# Audio_Output_XLR2.net
KiCad netlist of a schematic drawn in Altium Designer
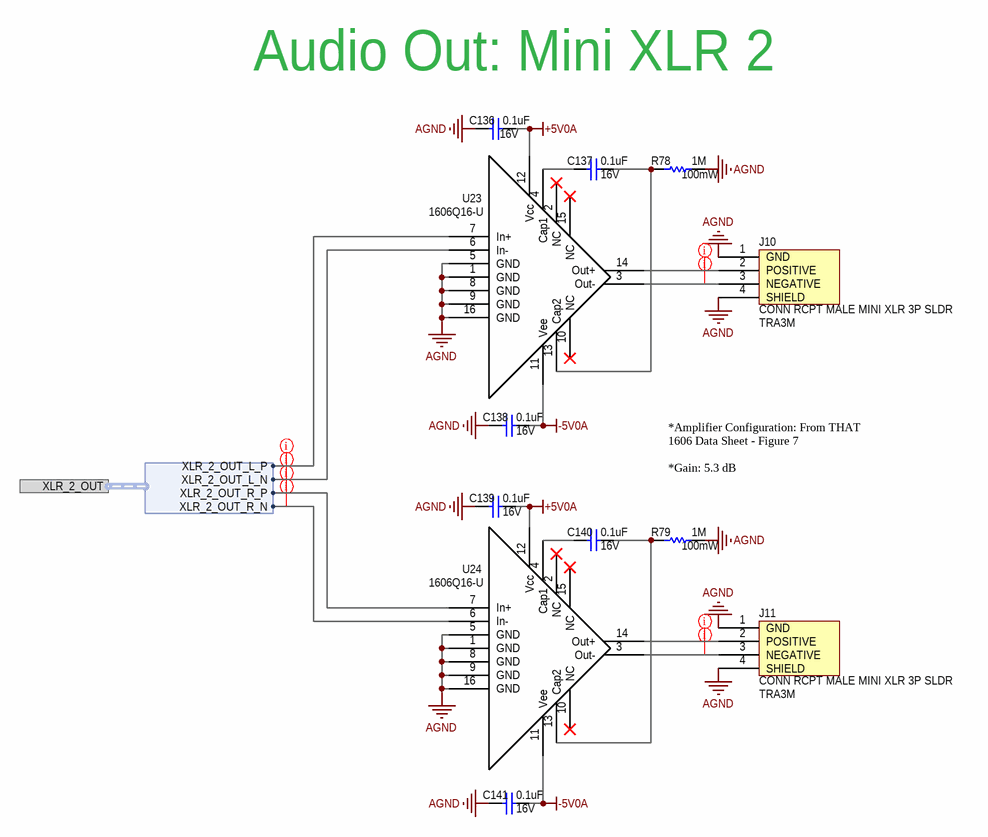
[diagram p0: Audio_Output_XLR2.SchDoc]

(export (version "E")
  (design (tool "Eeschema 10.0.6"))
  (components
    (comp (ref "C136")
      (value "CL10F104ZO8NNNC")
      (footprint "3-0603_L")
      (description "CAP CER 0.1UF 16V Y5V 0603")
      (fields
        (field (name "MANUFACTURER") "Samsung")
        (field (name "TOLERANCE") "80%")
        (field (name "VOLTAGE RATING") "16V")
        (field (name "CAPACITANCE") "0.1uF")
      )
      (libsource (lib "Schematic_Components_CD") (part "CL10F104ZO8NNNC"))
    )
    (comp (ref "C137")
      (value "CL10F104ZO8NNNC")
      (footprint "3-0603_L")
      (description "CAP CER 0.1UF 16V Y5V 0603")
      (fields
        (field (name "MANUFACTURER") "Samsung")
        (field (name "TOLERANCE") "80%")
        (field (name "VOLTAGE RATING") "16V")
        (field (name "CAPACITANCE") "0.1uF")
      )
      (libsource (lib "Schematic_Components_CD") (part "CL10F104ZO8NNNC"))
    )
    (comp (ref "C138")
      (value "CL10F104ZO8NNNC")
      (footprint "3-0603_L")
      (description "CAP CER 0.1UF 16V Y5V 0603")
      (fields
        (field (name "MANUFACTURER") "Samsung")
        (field (name "TOLERANCE") "80%")
        (field (name "VOLTAGE RATING") "16V")
        (field (name "CAPACITANCE") "0.1uF")
      )
      (libsource (lib "Schematic_Components_CD") (part "CL10F104ZO8NNNC"))
    )
    (comp (ref "C139")
      (value "CL10F104ZO8NNNC")
      (footprint "3-0603_L")
      (description "CAP CER 0.1UF 16V Y5V 0603")
      (fields
        (field (name "MANUFACTURER") "Samsung")
        (field (name "TOLERANCE") "80%")
        (field (name "VOLTAGE RATING") "16V")
        (field (name "CAPACITANCE") "0.1uF")
      )
      (libsource (lib "Schematic_Components_CD") (part "CL10F104ZO8NNNC"))
    )
    (comp (ref "C140")
      (value "CL10F104ZO8NNNC")
      (footprint "3-0603_L")
      (description "CAP CER 0.1UF 16V Y5V 0603")
      (fields
        (field (name "MANUFACTURER") "Samsung")
        (field (name "TOLERANCE") "80%")
        (field (name "VOLTAGE RATING") "16V")
        (field (name "CAPACITANCE") "0.1uF")
      )
      (libsource (lib "Schematic_Components_CD") (part "CL10F104ZO8NNNC"))
    )
    (comp (ref "C141")
      (value "CL10F104ZO8NNNC")
      (footprint "3-0603_L")
      (description "CAP CER 0.1UF 16V Y5V 0603")
      (fields
        (field (name "MANUFACTURER") "Samsung")
        (field (name "TOLERANCE") "80%")
        (field (name "VOLTAGE RATING") "16V")
        (field (name "CAPACITANCE") "0.1uF")
      )
      (libsource (lib "Schematic_Components_CD") (part "CL10F104ZO8NNNC"))
    )
    (comp (ref "J10")
      (value "CONN RCPT MALE MINI XLR 3P SLDR")
      (footprint "TRA3M")
      (description "3 Position Circular Connector Receptacle, Male Pins Solder Silver")
      (fields (field (name "MANUFACTURER") "Switchcraft") (field (name "MANUFACTURER PART NUMBER") "TRA3M"))
      (libsource (lib "Schematic_Components_CD") (part "TRA3M"))
    )
    (comp (ref "J11")
      (value "CONN RCPT MALE MINI XLR 3P SLDR")
      (footprint "TRA3M")
      (description "3 Position Circular Connector Receptacle, Male Pins Solder Silver")
      (fields (field (name "MANUFACTURER") "Switchcraft") (field (name "MANUFACTURER PART NUMBER") "TRA3M"))
      (libsource (lib "Schematic_Components_CD") (part "TRA3M"))
    )
    (comp (ref "R78")
      (value "RMCF0603FG1M00")
      (footprint "3-0603_R_L")
      (description "RES 1M OHM 1% 1/10W 0603")
      (fields
        (field (name "MANUFACTURER") "Stackpole Electronics")
        (field (name "TOLERANCE") "1%")
        (field (name "MAX POWER DISSIPATION") "100mW")
        (field (name "RESISTANCE") "1M")
      )
      (libsource (lib "Schematic_Components_CD") (part "RMCF0603FG1M00"))
    )
    (comp (ref "R79")
      (value "RMCF0603FG1M00")
      (footprint "3-0603_R_L")
      (description "RES 1M OHM 1% 1/10W 0603")
      (fields
        (field (name "MANUFACTURER") "Stackpole Electronics")
        (field (name "TOLERANCE") "1%")
        (field (name "MAX POWER DISSIPATION") "100mW")
        (field (name "RESISTANCE") "1M")
      )
      (libsource (lib "Schematic_Components_CD") (part "RMCF0603FG1M00"))
    )
    (comp (ref "U23")
      (value "1606Q16-U")
      (footprint "SOP64P600X175-16N")
      (description "Audio Amplifiers Balanced Audio Line Driver IC")
      (fields (field (name "MANUFACTURER") "THAT") (field (name "MANUFACTURER PART NUMBER") "1606Q16-U"))
      (libsource (lib "Schematic_Components_CD") (part "1606Q16-U"))
    )
    (comp (ref "U24")
      (value "1606Q16-U")
      (footprint "SOP64P600X175-16N")
      (description "Audio Amplifiers Balanced Audio Line Driver IC")
      (fields (field (name "MANUFACTURER") "THAT") (field (name "MANUFACTURER PART NUMBER") "1606Q16-U"))
      (libsource (lib "Schematic_Components_CD") (part "1606Q16-U"))
    )
  )
  (nets
    (net (code "2") (name "+5V0A") (class "Default")
      (node (ref "C136") (pin "1") (pinfunction "1_1") (pintype "passive"))
      (node (ref "C139") (pin "1") (pinfunction "1_1") (pintype "passive"))
      (node (ref "U23") (pin "12") (pinfunction "Vcc_12") (pintype "passive"))
      (node (ref "U24") (pin "12") (pinfunction "Vcc_12") (pintype "passive"))
    )
    (net (code "3") (name "-5V0A") (class "Default")
      (node (ref "C138") (pin "1") (pinfunction "1_1") (pintype "passive"))
      (node (ref "C141") (pin "1") (pinfunction "1_1") (pintype "passive"))
      (node (ref "U23") (pin "11") (pinfunction "Vee_11") (pintype "passive"))
      (node (ref "U24") (pin "11") (pinfunction "Vee_11") (pintype "passive"))
    )
    (net (code "4") (name "/XLR_2_OUT_L_N") (class "Default")
      (node (ref "U23") (pin "6") (pinfunction "In-_6") (pintype "passive"))
    )
    (net (code "5") (name "/XLR_2_OUT_L_P") (class "Default")
      (node (ref "U23") (pin "7") (pinfunction "In+_7") (pintype "passive"))
    )
    (net (code "6") (name "/XLR_2_OUT_R_N") (class "Default")
      (node (ref "U24") (pin "6") (pinfunction "In-_6") (pintype "passive"))
    )
    (net (code "7") (name "/XLR_2_OUT_R_P") (class "Default")
      (node (ref "U24") (pin "7") (pinfunction "In+_7") (pintype "passive"))
    )
    (net (code "9") (name "AGND") (class "Default")
      (node (ref "C136") (pin "2") (pinfunction "2_2") (pintype "passive"))
      (node (ref "C138") (pin "2") (pinfunction "2_2") (pintype "passive"))
      (node (ref "C139") (pin "2") (pinfunction "2_2") (pintype "passive"))
      (node (ref "C141") (pin "2") (pinfunction "2_2") (pintype "passive"))
      (node (ref "J10") (pin "1") (pinfunction "GND_1") (pintype "passive"))
      (node (ref "J10") (pin "4") (pinfunction "SHIELD_4") (pintype "passive"))
      (node (ref "J11") (pin "1") (pinfunction "GND_1") (pintype "passive"))
      (node (ref "J11") (pin "4") (pinfunction "SHIELD_4") (pintype "passive"))
      (node (ref "R78") (pin "2") (pinfunction "2_2") (pintype "passive"))
      (node (ref "R79") (pin "2") (pinfunction "2_2") (pintype "passive"))
      (node (ref "U23") (pin "1") (pinfunction "GND_1") (pintype "passive"))
      (node (ref "U23") (pin "16") (pinfunction "GND_16") (pintype "passive"))
      (node (ref "U23") (pin "5") (pinfunction "GND_5") (pintype "passive"))
      (node (ref "U23") (pin "8") (pinfunction "GND_8") (pintype "passive"))
      (node (ref "U23") (pin "9") (pinfunction "GND_9") (pintype "passive"))
      (node (ref "U24") (pin "1") (pinfunction "GND_1") (pintype "passive"))
      (node (ref "U24") (pin "16") (pinfunction "GND_16") (pintype "passive"))
      (node (ref "U24") (pin "5") (pinfunction "GND_5") (pintype "passive"))
      (node (ref "U24") (pin "8") (pinfunction "GND_8") (pintype "passive"))
      (node (ref "U24") (pin "9") (pinfunction "GND_9") (pintype "passive"))
    )
    (net (code "10") (name "Net-(J10-NEGATIVE)") (class "Default")
      (node (ref "J10") (pin "3") (pinfunction "NEGATIVE_3") (pintype "passive"))
      (node (ref "U23") (pin "3") (pinfunction "Out-_3") (pintype "passive"))
    )
    (net (code "11") (name "Net-(J10-POSITIVE)") (class "Default")
      (node (ref "J10") (pin "2") (pinfunction "POSITIVE_2") (pintype "passive"))
      (node (ref "U23") (pin "14") (pinfunction "Out+_14") (pintype "passive"))
    )
    (net (code "12") (name "Net-(J11-NEGATIVE)") (class "Default")
      (node (ref "J11") (pin "3") (pinfunction "NEGATIVE_3") (pintype "passive"))
      (node (ref "U24") (pin "3") (pinfunction "Out-_3") (pintype "passive"))
    )
    (net (code "13") (name "Net-(J11-POSITIVE)") (class "Default")
      (node (ref "J11") (pin "2") (pinfunction "POSITIVE_2") (pintype "passive"))
      (node (ref "U24") (pin "14") (pinfunction "Out+_14") (pintype "passive"))
    )
    (net (code "14") (name "Net-(U23-Cap1)") (class "Default")
      (node (ref "C137") (pin "2") (pinfunction "2_2") (pintype "passive"))
      (node (ref "U23") (pin "4") (pinfunction "Cap1_4") (pintype "passive"))
    )
    (net (code "15") (name "Net-(U23-Cap2)") (class "Default")
      (node (ref "C137") (pin "1") (pinfunction "1_1") (pintype "passive"))
      (node (ref "R78") (pin "1") (pinfunction "1_1") (pintype "passive"))
      (node (ref "U23") (pin "13") (pinfunction "Cap2_13") (pintype "passive"))
    )
    (net (code "16") (name "Net-(U24-Cap1)") (class "Default")
      (node (ref "C140") (pin "2") (pinfunction "2_2") (pintype "passive"))
      (node (ref "U24") (pin "4") (pinfunction "Cap1_4") (pintype "passive"))
    )
    (net (code "17") (name "Net-(U24-Cap2)") (class "Default")
      (node (ref "C140") (pin "1") (pinfunction "1_1") (pintype "passive"))
      (node (ref "R79") (pin "1") (pinfunction "1_1") (pintype "passive"))
      (node (ref "U24") (pin "13") (pinfunction "Cap2_13") (pintype "passive"))
    )
    (net (code "18") (name "unconnected-(U23-NC-Pad2)") (class "Default")
      (node (ref "U23") (pin "2") (pinfunction "NC_2") (pintype "passive+no_connect"))
    )
    (net (code "19") (name "unconnected-(U23-NC-Pad10)") (class "Default")
      (node (ref "U23") (pin "10") (pinfunction "NC_10") (pintype "passive+no_connect"))
    )
    (net (code "20") (name "unconnected-(U23-NC-Pad15)") (class "Default")
      (node (ref "U23") (pin "15") (pinfunction "NC_15") (pintype "passive+no_connect"))
    )
    (net (code "21") (name "unconnected-(U24-NC-Pad2)") (class "Default")
      (node (ref "U24") (pin "2") (pinfunction "NC_2") (pintype "passive+no_connect"))
    )
    (net (code "22") (name "unconnected-(U24-NC-Pad10)") (class "Default")
      (node (ref "U24") (pin "10") (pinfunction "NC_10") (pintype "passive+no_connect"))
    )
    (net (code "23") (name "unconnected-(U24-NC-Pad15)") (class "Default")
      (node (ref "U24") (pin "15") (pinfunction "NC_15") (pintype "passive+no_connect"))
    )
  )
)
